# Lab2_Scheme.net
KiCad netlist of a schematic drawn in Altium Designer
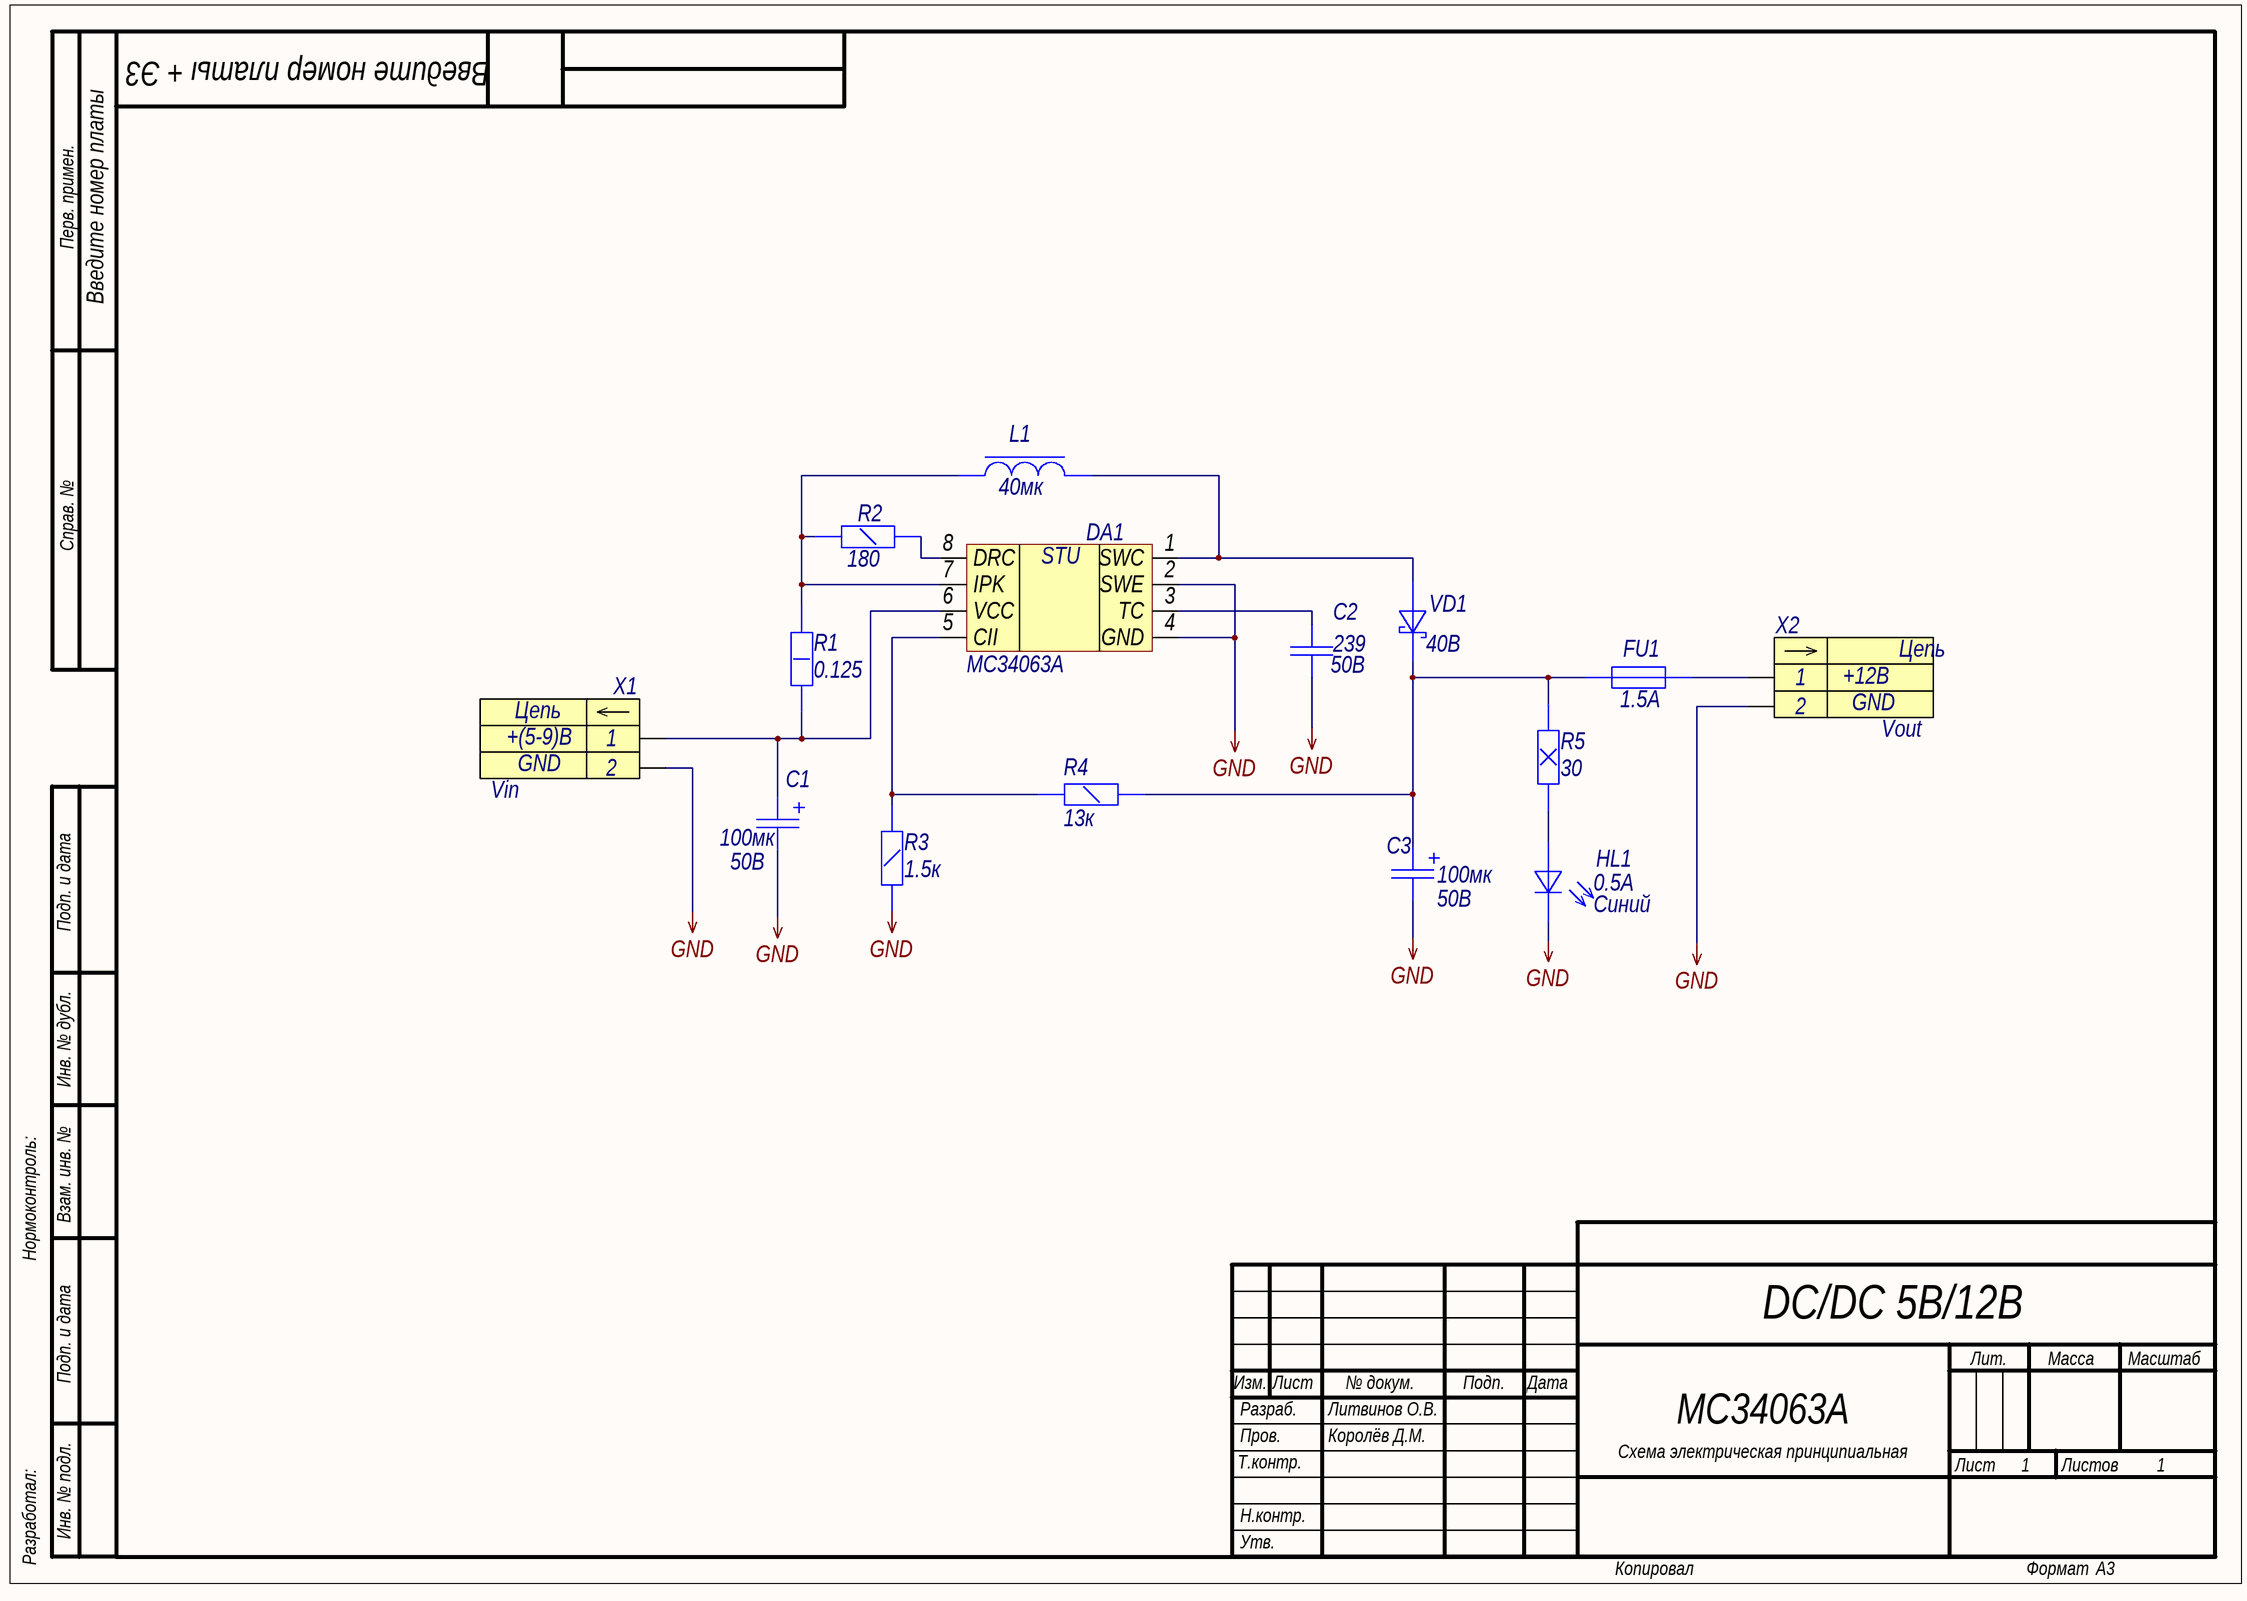
[diagram p0: Lab2_Scheme.SchDoc]

(export (version "E")
  (design (tool "Eeschema 10.0.6"))
  (components
    (comp (ref "C1")
      (value "Capacitor-E")
      (footprint "C1206")
      (fields
        (field (name "ЁМКОСТЬ") "100мк")
        (field (name "НАПРЯЖЕНИЕ") "50В")
        (field (name "PUBLISHER") "Олег Литвинов")
      )
      (libsource (lib "Capacitor GOST") (part "Capacitor-E"))
    )
    (comp (ref "C2")
      (value "Capacitor")
      (footprint "R0805")
      (fields
        (field (name "ЁМКОСТЬ") "239")
        (field (name "НАПРЯЖЕНИЕ") "50В")
        (field (name "PUBLISHER") "Andrew Danich")
      )
      (libsource (lib "Capacitor GOST") (part "Capacitor"))
    )
    (comp (ref "C3")
      (value "Capacitor-E")
      (footprint "C1206")
      (fields
        (field (name "ЁМКОСТЬ") "100мк")
        (field (name "НАПРЯЖЕНИЕ") "50В")
        (field (name "PUBLISHER") "Олег Литвинов")
      )
      (libsource (lib "Capacitor GOST") (part "Capacitor-E"))
    )
    (comp (ref "DA1")
      (value "MC34063A")
      (footprint "PCBComponent_1")
      (libsource (lib "MCP2200_UART_USB") (part "MC34063A"))
    )
    (comp (ref "FU1")
      (value "1.5A")
      (footprint "F1812")
      (fields (field (name "Comment") "Fuse"))
      (libsource (lib "Fuse_GOST") (part "Fuse"))
    )
    (comp (ref "HL1")
      (value "LED_3V")
      (footprint "LD0805")
      (fields
        (field (name "ПРЯМОЙ ТОК") "0.5А")
        (field (name "ЦВЕТ") "Синий")
        (field (name "PUBLISHER") "Andrew Danich")
      )
      (libsource (lib "Led GOST") (part "Led-1"))
    )
    (comp (ref "L1")
      (value "40мк")
      (footprint "МДГ-2")
      (fields
        (field (name "PART NUMBER") "КИВ18-100")
        (field (name "TOLERANCE") "±10%")
        (field (name "MANUFACTURER") "ОАО \"МСТАТОР\"")
        (field (name "PUBLISHER") "Andrew Danich")
      )
      (libsource (lib "Lib_GOST") (part "Coil"))
    )
    (comp (ref "R1")
      (value "0.125")
      (footprint "R0805")
      (fields (field (name "Comment") "Resistor_1,0W"))
      (libsource (lib "Resistor_GOST") (part "Resistor_1,0W"))
    )
    (comp (ref "R2")
      (value "Resistor_0,25W")
      (footprint "R0805")
      (fields (field (name "СОПРОТИВЛЕНИЕ") "180"))
      (libsource (lib "Resistor_GOST") (part "Resistor_0,25W"))
    )
    (comp (ref "R3")
      (value "1.5к")
      (footprint "R0805")
      (fields (field (name "Comment") "Resistor_0,25W"))
      (libsource (lib "Resistor_GOST") (part "Resistor_0,25W"))
    )
    (comp (ref "R4")
      (value "13к")
      (fields (field (name "Comment") "Resistor_0,25W"))
      (libsource (lib "Resistor_GOST") (part "Resistor_0,25W"))
    )
    (comp (ref "R5")
      (value "Resistor_10,0W")
      (footprint "R0805")
      (fields (field (name "СОПРОТИВЛЕНИЕ") "30"))
      (libsource (lib "Resistor_GOST") (part "Resistor_10,0W"))
    )
    (comp (ref "VD1")
      (value "Schottky")
      (footprint "DO-214AC")
      (description "BYV10-40")
      (fields (field (name "МАКСИМАЛЬНОЕ ОБРАТНОЕ НАПРЯЖЕНИЕ") "40В"))
      (libsource (lib "Diode_GOST") (part "Schottky"))
    )
    (comp (ref "X1")
      (value "Vin")
      (footprint "WF-2")
      (fields (field (name "U") "+(5-9)В") (field (name "GND") "GND") (field (name "CREATE") "DeathSpeaker"))
      (libsource (lib "MCP2200_UART_USB") (part "Vin"))
    )
    (comp (ref "X2")
      (value "Vout")
      (footprint "CWF-2")
      (fields (field (name "U") "+12В") (field (name "GND") "GND") (field (name "CREATE") "DeathSpeaker"))
      (libsource (lib "MCP2200_UART_USB") (part "Vout"))
    )
  )
  (nets
    (net (code "1") (name "GND") (class "Default")
      (node (ref "C1") (pin "2") (pinfunction "2_2") (pintype "passive"))
      (node (ref "C2") (pin "1") (pinfunction "1_1") (pintype "passive"))
      (node (ref "C3") (pin "2") (pinfunction "2_2") (pintype "passive"))
      (node (ref "DA1") (pin "2") (pinfunction "SWE_2") (pintype "passive"))
      (node (ref "DA1") (pin "4") (pinfunction "GND_4") (pintype "passive"))
      (node (ref "HL1") (pin "2") (pinfunction "К_2") (pintype "passive"))
      (node (ref "R3") (pin "1") (pinfunction "1_1") (pintype "passive"))
      (node (ref "X1") (pin "2") (pinfunction "2_2") (pintype "passive"))
      (node (ref "X2") (pin "2") (pinfunction "2_2") (pintype "passive"))
    )
    (net (code "2") (name "Net-(DA1-CII)") (class "Default")
      (node (ref "DA1") (pin "5") (pinfunction "CII_5") (pintype "passive"))
      (node (ref "R3") (pin "2") (pinfunction "2_2") (pintype "passive"))
      (node (ref "R4") (pin "1") (pinfunction "1_1") (pintype "passive"))
    )
    (net (code "3") (name "Net-(DA1-DRC)") (class "Default")
      (node (ref "DA1") (pin "8") (pinfunction "DRC_8") (pintype "passive"))
      (node (ref "R2") (pin "2") (pinfunction "2_2") (pintype "passive"))
    )
    (net (code "4") (name "Net-(DA1-IPK)") (class "Default")
      (node (ref "DA1") (pin "7") (pinfunction "IPK_7") (pintype "passive"))
      (node (ref "L1") (pin "1") (pinfunction "1_1") (pintype "passive"))
      (node (ref "R1") (pin "2") (pinfunction "2_2") (pintype "passive"))
      (node (ref "R2") (pin "1") (pinfunction "1_1") (pintype "passive"))
    )
    (net (code "5") (name "Net-(DA1-SWC)") (class "Default")
      (node (ref "DA1") (pin "1") (pinfunction "SWC_1") (pintype "passive"))
      (node (ref "L1") (pin "2") (pinfunction "2_2") (pintype "passive"))
      (node (ref "VD1") (pin "1") (pinfunction "А_1") (pintype "passive"))
    )
    (net (code "6") (name "Net-(DA1-TC)") (class "Default")
      (node (ref "C2") (pin "2") (pinfunction "2_2") (pintype "passive"))
      (node (ref "DA1") (pin "3") (pinfunction "TC_3") (pintype "passive"))
    )
    (net (code "7") (name "Net-(DA1-VCC)") (class "Default")
      (node (ref "C1") (pin "1") (pinfunction "1_1") (pintype "passive"))
      (node (ref "DA1") (pin "6") (pinfunction "VCC_6") (pintype "passive"))
      (node (ref "R1") (pin "1") (pinfunction "1_1") (pintype "passive"))
      (node (ref "X1") (pin "1") (pinfunction "1_1") (pintype "passive"))
    )
    (net (code "8") (name "Net-(FU1-Pad1)") (class "Default")
      (node (ref "FU1") (pin "1") (pinfunction "1_1") (pintype "passive"))
      (node (ref "X2") (pin "1") (pinfunction "1_1") (pintype "passive"))
    )
    (net (code "9") (name "Net-(HL1-А)") (class "Default")
      (node (ref "HL1") (pin "1") (pinfunction "А_1") (pintype "passive"))
      (node (ref "R5") (pin "1") (pinfunction "1_1") (pintype "passive"))
    )
    (net (code "10") (name "Net-(VD1-К)") (class "Default")
      (node (ref "C3") (pin "1") (pinfunction "1_1") (pintype "passive"))
      (node (ref "FU1") (pin "2") (pinfunction "2_2") (pintype "passive"))
      (node (ref "R4") (pin "2") (pinfunction "2_2") (pintype "passive"))
      (node (ref "R5") (pin "2") (pinfunction "2_2") (pintype "passive"))
      (node (ref "VD1") (pin "2") (pinfunction "К_2") (pintype "passive"))
    )
  )
)
